# DM_V1_headers_misc.net
KiCad netlist of a schematic drawn in Altium Designer
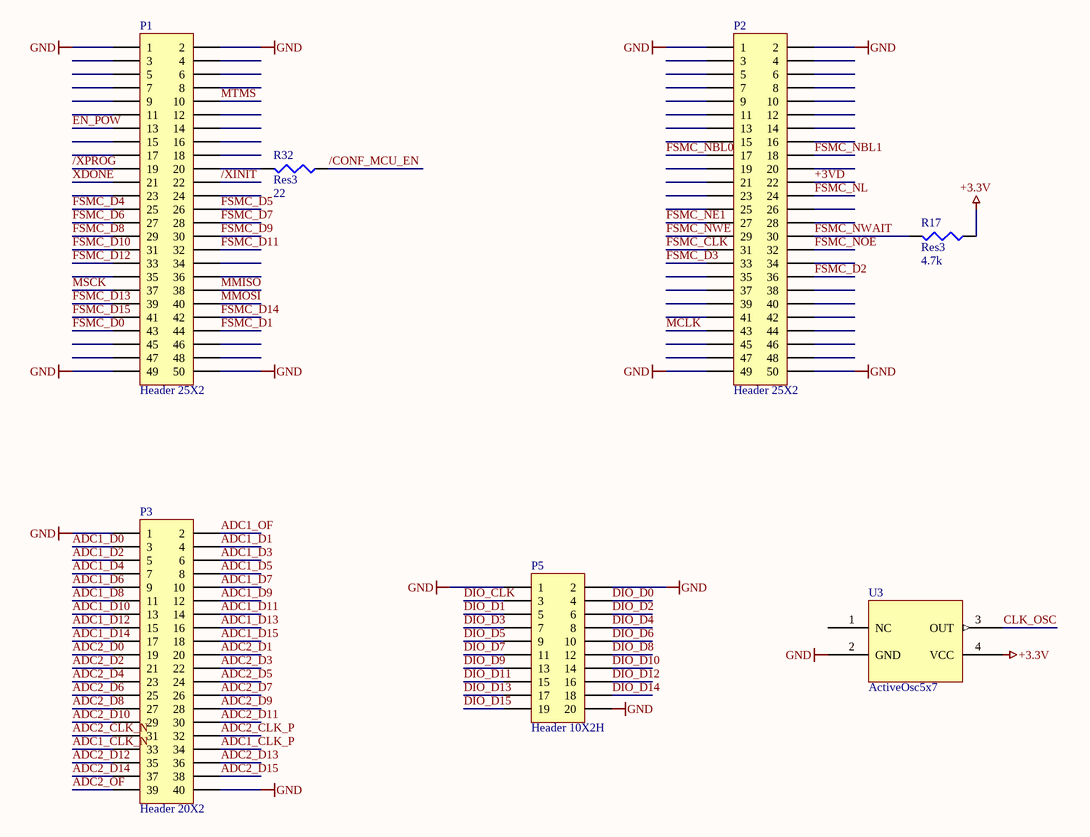
[diagram p0: DM_V1_headers_misc.SchDoc]

(export (version "E")
  (design (tool "Eeschema 10.0.6"))
  (components
    (comp (ref "P1")
      (value "Header 25X2")
      (footprint "HDR2X25")
      (description "Header, 25-Pin, Dual row")
      (fields (field (name "PUBLISHER") "Altium Limited"))
      (libsource (lib "Miscellaneous Connectors") (part "Header 25X2"))
    )
    (comp (ref "P2")
      (value "Header 25X2")
      (footprint "HDR2X25")
      (description "Header, 25-Pin, Dual row")
      (fields (field (name "PUBLISHER") "Altium Limited"))
      (libsource (lib "Miscellaneous Connectors") (part "Header 25X2"))
    )
    (comp (ref "P3")
      (value "Header 20X2")
      (footprint "HDR2X20")
      (description "Header, 20-Pin, Dual row")
      (fields (field (name "PUBLISHER") "Altium Limited"))
      (libsource (lib "Miscellaneous Connectors") (part "Header 20X2"))
    )
    (comp (ref "P5")
      (value "Header 10X2H")
      (footprint "HDR2X10H")
      (description "Header, 10-Pin, Dual row, Right Angle")
      (fields (field (name "PUBLISHER") "Altium Limited"))
      (libsource (lib "Miscellaneous Connectors") (part "Header 10X2H"))
    )
    (comp (ref "R17")
      (value "Res3")
      (footprint "J1-0603")
      (description "Resistor")
      (fields (field (name "ALTIUM_VALUE") "4.7k") (field (name "PUBLISHER") "Altium Limited"))
      (libsource (lib "Miscellaneous Devices") (part "Res3"))
    )
    (comp (ref "R32")
      (value "Res3")
      (footprint "J1-0603")
      (description "Resistor")
      (fields (field (name "ALTIUM_VALUE") "22") (field (name "PUBLISHER") "Altium Limited"))
      (libsource (lib "Miscellaneous Devices") (part "Res3"))
    )
    (comp (ref "U3")
      (value "ActiveOsc5x7")
      (footprint "ACT_OSC")
      (libsource (lib "Schlib2") (part "ActiveOsc5x7"))
    )
  )
  (nets
    (net (code "1") (name "+3.3V") (class "Default")
      (node (ref "R17") (pin "1") (pinfunction "1_1") (pintype "passive"))
      (node (ref "U3") (pin "4") (pinfunction "VCC_4") (pintype "power_in"))
    )
    (net (code "2") (name "/+3VD") (class "Default")
      (node (ref "P2") (pin "22") (pinfunction "22_22") (pintype "passive"))
    )
    (net (code "3") (name "/ADC1_CLK_N") (class "Default")
      (node (ref "P3") (pin "33") (pinfunction "33_33") (pintype "passive"))
    )
    (net (code "4") (name "/ADC1_CLK_P") (class "Default")
      (node (ref "P3") (pin "34") (pinfunction "34_34") (pintype "passive"))
    )
    (net (code "5") (name "/ADC1_D0") (class "Default")
      (node (ref "P3") (pin "3") (pinfunction "3_3") (pintype "passive"))
    )
    (net (code "6") (name "/ADC1_D1") (class "Default")
      (node (ref "P3") (pin "4") (pinfunction "4_4") (pintype "passive"))
    )
    (net (code "7") (name "/ADC1_D2") (class "Default")
      (node (ref "P3") (pin "5") (pinfunction "5_5") (pintype "passive"))
    )
    (net (code "8") (name "/ADC1_D3") (class "Default")
      (node (ref "P3") (pin "6") (pinfunction "6_6") (pintype "passive"))
    )
    (net (code "9") (name "/ADC1_D4") (class "Default")
      (node (ref "P3") (pin "7") (pinfunction "7_7") (pintype "passive"))
    )
    (net (code "10") (name "/ADC1_D5") (class "Default")
      (node (ref "P3") (pin "8") (pinfunction "8_8") (pintype "passive"))
    )
    (net (code "11") (name "/ADC1_D6") (class "Default")
      (node (ref "P3") (pin "9") (pinfunction "9_9") (pintype "passive"))
    )
    (net (code "12") (name "/ADC1_D7") (class "Default")
      (node (ref "P3") (pin "10") (pinfunction "10_10") (pintype "passive"))
    )
    (net (code "13") (name "/ADC1_D8") (class "Default")
      (node (ref "P3") (pin "11") (pinfunction "11_11") (pintype "passive"))
    )
    (net (code "14") (name "/ADC1_D9") (class "Default")
      (node (ref "P3") (pin "12") (pinfunction "12_12") (pintype "passive"))
    )
    (net (code "15") (name "/ADC1_D10") (class "Default")
      (node (ref "P3") (pin "13") (pinfunction "13_13") (pintype "passive"))
    )
    (net (code "16") (name "/ADC1_D11") (class "Default")
      (node (ref "P3") (pin "14") (pinfunction "14_14") (pintype "passive"))
    )
    (net (code "17") (name "/ADC1_D12") (class "Default")
      (node (ref "P3") (pin "15") (pinfunction "15_15") (pintype "passive"))
    )
    (net (code "18") (name "/ADC1_D13") (class "Default")
      (node (ref "P3") (pin "16") (pinfunction "16_16") (pintype "passive"))
    )
    (net (code "19") (name "/ADC1_D14") (class "Default")
      (node (ref "P3") (pin "17") (pinfunction "17_17") (pintype "passive"))
    )
    (net (code "20") (name "/ADC1_D15") (class "Default")
      (node (ref "P3") (pin "18") (pinfunction "18_18") (pintype "passive"))
    )
    (net (code "21") (name "/ADC1_OF") (class "Default")
      (node (ref "P3") (pin "2") (pinfunction "2_2") (pintype "passive"))
    )
    (net (code "22") (name "/ADC2_CLK_N") (class "Default")
      (node (ref "P3") (pin "31") (pinfunction "31_31") (pintype "passive"))
    )
    (net (code "23") (name "/ADC2_CLK_P") (class "Default")
      (node (ref "P3") (pin "32") (pinfunction "32_32") (pintype "passive"))
    )
    (net (code "24") (name "/ADC2_D0") (class "Default")
      (node (ref "P3") (pin "19") (pinfunction "19_19") (pintype "passive"))
    )
    (net (code "25") (name "/ADC2_D1") (class "Default")
      (node (ref "P3") (pin "20") (pinfunction "20_20") (pintype "passive"))
    )
    (net (code "26") (name "/ADC2_D2") (class "Default")
      (node (ref "P3") (pin "21") (pinfunction "21_21") (pintype "passive"))
    )
    (net (code "27") (name "/ADC2_D3") (class "Default")
      (node (ref "P3") (pin "22") (pinfunction "22_22") (pintype "passive"))
    )
    (net (code "28") (name "/ADC2_D4") (class "Default")
      (node (ref "P3") (pin "23") (pinfunction "23_23") (pintype "passive"))
    )
    (net (code "29") (name "/ADC2_D5") (class "Default")
      (node (ref "P3") (pin "24") (pinfunction "24_24") (pintype "passive"))
    )
    (net (code "30") (name "/ADC2_D6") (class "Default")
      (node (ref "P3") (pin "25") (pinfunction "25_25") (pintype "passive"))
    )
    (net (code "31") (name "/ADC2_D7") (class "Default")
      (node (ref "P3") (pin "26") (pinfunction "26_26") (pintype "passive"))
    )
    (net (code "32") (name "/ADC2_D8") (class "Default")
      (node (ref "P3") (pin "27") (pinfunction "27_27") (pintype "passive"))
    )
    (net (code "33") (name "/ADC2_D9") (class "Default")
      (node (ref "P3") (pin "28") (pinfunction "28_28") (pintype "passive"))
    )
    (net (code "34") (name "/ADC2_D10") (class "Default")
      (node (ref "P3") (pin "29") (pinfunction "29_29") (pintype "passive"))
    )
    (net (code "35") (name "/ADC2_D11") (class "Default")
      (node (ref "P3") (pin "30") (pinfunction "30_30") (pintype "passive"))
    )
    (net (code "36") (name "/ADC2_D12") (class "Default")
      (node (ref "P3") (pin "35") (pinfunction "35_35") (pintype "passive"))
    )
    (net (code "37") (name "/ADC2_D13") (class "Default")
      (node (ref "P3") (pin "36") (pinfunction "36_36") (pintype "passive"))
    )
    (net (code "38") (name "/ADC2_D14") (class "Default")
      (node (ref "P3") (pin "37") (pinfunction "37_37") (pintype "passive"))
    )
    (net (code "39") (name "/ADC2_D15") (class "Default")
      (node (ref "P3") (pin "38") (pinfunction "38_38") (pintype "passive"))
    )
    (net (code "40") (name "/ADC2_OF") (class "Default")
      (node (ref "P3") (pin "39") (pinfunction "39_39") (pintype "passive"))
    )
    (net (code "41") (name "/CLK_OSC") (class "Default")
      (node (ref "U3") (pin "3") (pinfunction "OUT_3") (pintype "output"))
    )
    (net (code "42") (name "/DIO_CLK") (class "Default")
      (node (ref "P5") (pin "3") (pinfunction "3_3") (pintype "passive"))
    )
    (net (code "43") (name "/DIO_D0") (class "Default")
      (node (ref "P5") (pin "4") (pinfunction "4_4") (pintype "passive"))
    )
    (net (code "44") (name "/DIO_D1") (class "Default")
      (node (ref "P5") (pin "5") (pinfunction "5_5") (pintype "passive"))
    )
    (net (code "45") (name "/DIO_D2") (class "Default")
      (node (ref "P5") (pin "6") (pinfunction "6_6") (pintype "passive"))
    )
    (net (code "46") (name "/DIO_D3") (class "Default")
      (node (ref "P5") (pin "7") (pinfunction "7_7") (pintype "passive"))
    )
    (net (code "47") (name "/DIO_D4") (class "Default")
      (node (ref "P5") (pin "8") (pinfunction "8_8") (pintype "passive"))
    )
    (net (code "48") (name "/DIO_D5") (class "Default")
      (node (ref "P5") (pin "9") (pinfunction "9_9") (pintype "passive"))
    )
    (net (code "49") (name "/DIO_D6") (class "Default")
      (node (ref "P5") (pin "10") (pinfunction "10_10") (pintype "passive"))
    )
    (net (code "50") (name "/DIO_D7") (class "Default")
      (node (ref "P5") (pin "11") (pinfunction "11_11") (pintype "passive"))
    )
    (net (code "51") (name "/DIO_D8") (class "Default")
      (node (ref "P5") (pin "12") (pinfunction "12_12") (pintype "passive"))
    )
    (net (code "52") (name "/DIO_D9") (class "Default")
      (node (ref "P5") (pin "13") (pinfunction "13_13") (pintype "passive"))
    )
    (net (code "53") (name "/DIO_D10") (class "Default")
      (node (ref "P5") (pin "14") (pinfunction "14_14") (pintype "passive"))
    )
    (net (code "54") (name "/DIO_D11") (class "Default")
      (node (ref "P5") (pin "15") (pinfunction "15_15") (pintype "passive"))
    )
    (net (code "55") (name "/DIO_D12") (class "Default")
      (node (ref "P5") (pin "16") (pinfunction "16_16") (pintype "passive"))
    )
    (net (code "56") (name "/DIO_D13") (class "Default")
      (node (ref "P5") (pin "17") (pinfunction "17_17") (pintype "passive"))
    )
    (net (code "57") (name "/DIO_D14") (class "Default")
      (node (ref "P5") (pin "18") (pinfunction "18_18") (pintype "passive"))
    )
    (net (code "58") (name "/DIO_D15") (class "Default")
      (node (ref "P5") (pin "19") (pinfunction "19_19") (pintype "passive"))
    )
    (net (code "59") (name "/EN_POW") (class "Default")
      (node (ref "P1") (pin "13") (pinfunction "13_13") (pintype "passive"))
    )
    (net (code "60") (name "/FSMC_CLK") (class "Default")
      (node (ref "P2") (pin "31") (pinfunction "31_31") (pintype "passive"))
    )
    (net (code "61") (name "/FSMC_D0") (class "Default")
      (node (ref "P1") (pin "43") (pinfunction "43_43") (pintype "passive"))
    )
    (net (code "62") (name "/FSMC_D1") (class "Default")
      (node (ref "P1") (pin "44") (pinfunction "44_44") (pintype "passive"))
    )
    (net (code "63") (name "/FSMC_D2") (class "Default")
      (node (ref "P2") (pin "36") (pinfunction "36_36") (pintype "passive"))
    )
    (net (code "64") (name "/FSMC_D3") (class "Default")
      (node (ref "P2") (pin "33") (pinfunction "33_33") (pintype "passive"))
    )
    (net (code "65") (name "/FSMC_D4") (class "Default")
      (node (ref "P1") (pin "25") (pinfunction "25_25") (pintype "passive"))
    )
    (net (code "66") (name "/FSMC_D5") (class "Default")
      (node (ref "P1") (pin "26") (pinfunction "26_26") (pintype "passive"))
    )
    (net (code "67") (name "/FSMC_D6") (class "Default")
      (node (ref "P1") (pin "27") (pinfunction "27_27") (pintype "passive"))
    )
    (net (code "68") (name "/FSMC_D7") (class "Default")
      (node (ref "P1") (pin "28") (pinfunction "28_28") (pintype "passive"))
    )
    (net (code "69") (name "/FSMC_D8") (class "Default")
      (node (ref "P1") (pin "29") (pinfunction "29_29") (pintype "passive"))
    )
    (net (code "70") (name "/FSMC_D9") (class "Default")
      (node (ref "P1") (pin "30") (pinfunction "30_30") (pintype "passive"))
    )
    (net (code "71") (name "/FSMC_D10") (class "Default")
      (node (ref "P1") (pin "31") (pinfunction "31_31") (pintype "passive"))
    )
    (net (code "72") (name "/FSMC_D11") (class "Default")
      (node (ref "P1") (pin "32") (pinfunction "32_32") (pintype "passive"))
    )
    (net (code "73") (name "/FSMC_D12") (class "Default")
      (node (ref "P1") (pin "33") (pinfunction "33_33") (pintype "passive"))
    )
    (net (code "74") (name "/FSMC_D13") (class "Default")
      (node (ref "P1") (pin "39") (pinfunction "39_39") (pintype "passive"))
    )
    (net (code "75") (name "/FSMC_D14") (class "Default")
      (node (ref "P1") (pin "42") (pinfunction "42_42") (pintype "passive"))
    )
    (net (code "76") (name "/FSMC_D15") (class "Default")
      (node (ref "P1") (pin "41") (pinfunction "41_41") (pintype "passive"))
    )
    (net (code "77") (name "/FSMC_NBL0") (class "Default")
      (node (ref "P2") (pin "17") (pinfunction "17_17") (pintype "passive"))
    )
    (net (code "78") (name "/FSMC_NBL1") (class "Default")
      (node (ref "P2") (pin "18") (pinfunction "18_18") (pintype "passive"))
    )
    (net (code "79") (name "/FSMC_NE1") (class "Default")
      (node (ref "P2") (pin "27") (pinfunction "27_27") (pintype "passive"))
    )
    (net (code "80") (name "/FSMC_NL") (class "Default")
      (node (ref "P2") (pin "24") (pinfunction "24_24") (pintype "passive"))
    )
    (net (code "81") (name "/FSMC_NOE") (class "Default")
      (node (ref "P2") (pin "32") (pinfunction "32_32") (pintype "passive"))
    )
    (net (code "82") (name "/FSMC_NWAIT") (class "Default")
      (node (ref "P2") (pin "30") (pinfunction "30_30") (pintype "passive"))
      (node (ref "R17") (pin "2") (pinfunction "2_2") (pintype "passive"))
    )
    (net (code "83") (name "/FSMC_NWE") (class "Default")
      (node (ref "P2") (pin "29") (pinfunction "29_29") (pintype "passive"))
    )
    (net (code "84") (name "/MCLK") (class "Default")
      (node (ref "P2") (pin "43") (pinfunction "43_43") (pintype "passive"))
    )
    (net (code "85") (name "/MMISO") (class "Default")
      (node (ref "P1") (pin "38") (pinfunction "38_38") (pintype "passive"))
    )
    (net (code "86") (name "/MMOSI") (class "Default")
      (node (ref "P1") (pin "40") (pinfunction "40_40") (pintype "passive"))
    )
    (net (code "87") (name "/MSCK") (class "Default")
      (node (ref "P1") (pin "37") (pinfunction "37_37") (pintype "passive"))
    )
    (net (code "88") (name "/MTMS") (class "Default")
      (node (ref "P1") (pin "10") (pinfunction "10_10") (pintype "passive"))
    )
    (net (code "89") (name "/XDONE") (class "Default")
      (node (ref "P1") (pin "21") (pinfunction "21_21") (pintype "passive"))
    )
    (net (code "90") (name "/{slash}CONF_MCU_EN") (class "Default")
      (node (ref "R32") (pin "1") (pinfunction "1_1") (pintype "passive"))
    )
    (net (code "91") (name "/{slash}XINIT") (class "Default")
      (node (ref "P1") (pin "22") (pinfunction "22_22") (pintype "passive"))
    )
    (net (code "92") (name "/{slash}XPROG") (class "Default")
      (node (ref "P1") (pin "19") (pinfunction "19_19") (pintype "passive"))
    )
    (net (code "93") (name "GND") (class "Default")
      (node (ref "P1") (pin "1") (pinfunction "1_1") (pintype "passive"))
      (node (ref "P1") (pin "2") (pinfunction "2_2") (pintype "passive"))
      (node (ref "P1") (pin "49") (pinfunction "49_49") (pintype "passive"))
      (node (ref "P1") (pin "50") (pinfunction "50_50") (pintype "passive"))
      (node (ref "P2") (pin "1") (pinfunction "1_1") (pintype "passive"))
      (node (ref "P2") (pin "2") (pinfunction "2_2") (pintype "passive"))
      (node (ref "P2") (pin "49") (pinfunction "49_49") (pintype "passive"))
      (node (ref "P2") (pin "50") (pinfunction "50_50") (pintype "passive"))
      (node (ref "P3") (pin "1") (pinfunction "1_1") (pintype "passive"))
      (node (ref "P3") (pin "40") (pinfunction "40_40") (pintype "passive"))
      (node (ref "P5") (pin "1") (pinfunction "1_1") (pintype "passive"))
      (node (ref "P5") (pin "2") (pinfunction "2_2") (pintype "passive"))
      (node (ref "P5") (pin "20") (pinfunction "20_20") (pintype "passive"))
      (node (ref "U3") (pin "2") (pinfunction "GND_2") (pintype "power_in"))
    )
    (net (code "94") (name "Net-(P1-Pad20)") (class "Default")
      (node (ref "P1") (pin "20") (pinfunction "20_20") (pintype "passive"))
      (node (ref "R32") (pin "2") (pinfunction "2_2") (pintype "passive"))
    )
    (net (code "95") (name "unconnected-(P1-Pad3)") (class "Default")
      (node (ref "P1") (pin "3") (pinfunction "3_3") (pintype "passive"))
    )
    (net (code "96") (name "unconnected-(P1-Pad4)") (class "Default")
      (node (ref "P1") (pin "4") (pinfunction "4_4") (pintype "passive"))
    )
    (net (code "97") (name "unconnected-(P1-Pad5)") (class "Default")
      (node (ref "P1") (pin "5") (pinfunction "5_5") (pintype "passive"))
    )
    (net (code "98") (name "unconnected-(P1-Pad6)") (class "Default")
      (node (ref "P1") (pin "6") (pinfunction "6_6") (pintype "passive"))
    )
    (net (code "99") (name "unconnected-(P1-Pad7)") (class "Default")
      (node (ref "P1") (pin "7") (pinfunction "7_7") (pintype "passive"))
    )
    (net (code "100") (name "unconnected-(P1-Pad8)") (class "Default")
      (node (ref "P1") (pin "8") (pinfunction "8_8") (pintype "passive"))
    )
    (net (code "101") (name "unconnected-(P1-Pad9)") (class "Default")
      (node (ref "P1") (pin "9") (pinfunction "9_9") (pintype "passive"))
    )
    (net (code "102") (name "unconnected-(P1-Pad11)") (class "Default")
      (node (ref "P1") (pin "11") (pinfunction "11_11") (pintype "passive"))
    )
    (net (code "103") (name "unconnected-(P1-Pad12)") (class "Default")
      (node (ref "P1") (pin "12") (pinfunction "12_12") (pintype "passive"))
    )
    (net (code "104") (name "unconnected-(P1-Pad14)") (class "Default")
      (node (ref "P1") (pin "14") (pinfunction "14_14") (pintype "passive"))
    )
    (net (code "105") (name "unconnected-(P1-Pad15)") (class "Default")
      (node (ref "P1") (pin "15") (pinfunction "15_15") (pintype "passive"))
    )
    (net (code "106") (name "unconnected-(P1-Pad16)") (class "Default")
      (node (ref "P1") (pin "16") (pinfunction "16_16") (pintype "passive"))
    )
    (net (code "107") (name "unconnected-(P1-Pad17)") (class "Default")
      (node (ref "P1") (pin "17") (pinfunction "17_17") (pintype "passive"))
    )
    (net (code "108") (name "unconnected-(P1-Pad18)") (class "Default")
      (node (ref "P1") (pin "18") (pinfunction "18_18") (pintype "passive"))
    )
    (net (code "109") (name "unconnected-(P1-Pad23)") (class "Default")
      (node (ref "P1") (pin "23") (pinfunction "23_23") (pintype "passive"))
    )
    (net (code "110") (name "unconnected-(P1-Pad24)") (class "Default")
      (node (ref "P1") (pin "24") (pinfunction "24_24") (pintype "passive"))
    )
    (net (code "111") (name "unconnected-(P1-Pad34)") (class "Default")
      (node (ref "P1") (pin "34") (pinfunction "34_34") (pintype "passive"))
    )
    (net (code "112") (name "unconnected-(P1-Pad35)") (class "Default")
      (node (ref "P1") (pin "35") (pinfunction "35_35") (pintype "passive"))
    )
    (net (code "113") (name "unconnected-(P1-Pad36)") (class "Default")
      (node (ref "P1") (pin "36") (pinfunction "36_36") (pintype "passive"))
    )
    (net (code "114") (name "unconnected-(P1-Pad45)") (class "Default")
      (node (ref "P1") (pin "45") (pinfunction "45_45") (pintype "passive"))
    )
    (net (code "115") (name "unconnected-(P1-Pad46)") (class "Default")
      (node (ref "P1") (pin "46") (pinfunction "46_46") (pintype "passive"))
    )
    (net (code "116") (name "unconnected-(P1-Pad47)") (class "Default")
      (node (ref "P1") (pin "47") (pinfunction "47_47") (pintype "passive"))
    )
    (net (code "117") (name "unconnected-(P1-Pad48)") (class "Default")
      (node (ref "P1") (pin "48") (pinfunction "48_48") (pintype "passive"))
    )
    (net (code "118") (name "unconnected-(P2-Pad3)") (class "Default")
      (node (ref "P2") (pin "3") (pinfunction "3_3") (pintype "passive"))
    )
    (net (code "119") (name "unconnected-(P2-Pad4)") (class "Default")
      (node (ref "P2") (pin "4") (pinfunction "4_4") (pintype "passive"))
    )
    (net (code "120") (name "unconnected-(P2-Pad5)") (class "Default")
      (node (ref "P2") (pin "5") (pinfunction "5_5") (pintype "passive"))
    )
    (net (code "121") (name "unconnected-(P2-Pad6)") (class "Default")
      (node (ref "P2") (pin "6") (pinfunction "6_6") (pintype "passive"))
    )
    (net (code "122") (name "unconnected-(P2-Pad7)") (class "Default")
      (node (ref "P2") (pin "7") (pinfunction "7_7") (pintype "passive"))
    )
    (net (code "123") (name "unconnected-(P2-Pad8)") (class "Default")
      (node (ref "P2") (pin "8") (pinfunction "8_8") (pintype "passive"))
    )
    (net (code "124") (name "unconnected-(P2-Pad9)") (class "Default")
      (node (ref "P2") (pin "9") (pinfunction "9_9") (pintype "passive"))
    )
    (net (code "125") (name "unconnected-(P2-Pad10)") (class "Default")
      (node (ref "P2") (pin "10") (pinfunction "10_10") (pintype "passive"))
    )
    (net (code "126") (name "unconnected-(P2-Pad11)") (class "Default")
      (node (ref "P2") (pin "11") (pinfunction "11_11") (pintype "passive"))
    )
    (net (code "127") (name "unconnected-(P2-Pad12)") (class "Default")
      (node (ref "P2") (pin "12") (pinfunction "12_12") (pintype "passive"))
    )
    (net (code "128") (name "unconnected-(P2-Pad13)") (class "Default")
      (node (ref "P2") (pin "13") (pinfunction "13_13") (pintype "passive"))
    )
    (net (code "129") (name "unconnected-(P2-Pad14)") (class "Default")
      (node (ref "P2") (pin "14") (pinfunction "14_14") (pintype "passive"))
    )
    (net (code "130") (name "unconnected-(P2-Pad15)") (class "Default")
      (node (ref "P2") (pin "15") (pinfunction "15_15") (pintype "passive"))
    )
    (net (code "131") (name "unconnected-(P2-Pad16)") (class "Default")
      (node (ref "P2") (pin "16") (pinfunction "16_16") (pintype "passive"))
    )
    (net (code "132") (name "unconnected-(P2-Pad19)") (class "Default")
      (node (ref "P2") (pin "19") (pinfunction "19_19") (pintype "passive"))
    )
    (net (code "133") (name "unconnected-(P2-Pad20)") (class "Default")
      (node (ref "P2") (pin "20") (pinfunction "20_20") (pintype "passive"))
    )
    (net (code "134") (name "unconnected-(P2-Pad21)") (class "Default")
      (node (ref "P2") (pin "21") (pinfunction "21_21") (pintype "passive"))
    )
    (net (code "135") (name "unconnected-(P2-Pad23)") (class "Default")
      (node (ref "P2") (pin "23") (pinfunction "23_23") (pintype "passive"))
    )
    (net (code "136") (name "unconnected-(P2-Pad25)") (class "Default")
      (node (ref "P2") (pin "25") (pinfunction "25_25") (pintype "passive"))
    )
    (net (code "137") (name "unconnected-(P2-Pad26)") (class "Default")
      (node (ref "P2") (pin "26") (pinfunction "26_26") (pintype "passive"))
    )
    (net (code "138") (name "unconnected-(P2-Pad28)") (class "Default")
      (node (ref "P2") (pin "28") (pinfunction "28_28") (pintype "passive"))
    )
    (net (code "139") (name "unconnected-(P2-Pad34)") (class "Default")
      (node (ref "P2") (pin "34") (pinfunction "34_34") (pintype "passive"))
    )
    (net (code "140") (name "unconnected-(P2-Pad35)") (class "Default")
      (node (ref "P2") (pin "35") (pinfunction "35_35") (pintype "passive"))
    )
    (net (code "141") (name "unconnected-(P2-Pad37)") (class "Default")
      (node (ref "P2") (pin "37") (pinfunction "37_37") (pintype "passive"))
    )
    (net (code "142") (name "unconnected-(P2-Pad38)") (class "Default")
      (node (ref "P2") (pin "38") (pinfunction "38_38") (pintype "passive"))
    )
    (net (code "143") (name "unconnected-(P2-Pad39)") (class "Default")
      (node (ref "P2") (pin "39") (pinfunction "39_39") (pintype "passive"))
    )
    (net (code "144") (name "unconnected-(P2-Pad40)") (class "Default")
      (node (ref "P2") (pin "40") (pinfunction "40_40") (pintype "passive"))
    )
    (net (code "145") (name "unconnected-(P2-Pad41)") (class "Default")
      (node (ref "P2") (pin "41") (pinfunction "41_41") (pintype "passive"))
    )
    (net (code "146") (name "unconnected-(P2-Pad42)") (class "Default")
      (node (ref "P2") (pin "42") (pinfunction "42_42") (pintype "passive"))
    )
    (net (code "147") (name "unconnected-(P2-Pad44)") (class "Default")
      (node (ref "P2") (pin "44") (pinfunction "44_44") (pintype "passive"))
    )
    (net (code "148") (name "unconnected-(P2-Pad45)") (class "Default")
      (node (ref "P2") (pin "45") (pinfunction "45_45") (pintype "passive"))
    )
    (net (code "149") (name "unconnected-(P2-Pad46)") (class "Default")
      (node (ref "P2") (pin "46") (pinfunction "46_46") (pintype "passive"))
    )
    (net (code "150") (name "unconnected-(P2-Pad47)") (class "Default")
      (node (ref "P2") (pin "47") (pinfunction "47_47") (pintype "passive"))
    )
    (net (code "151") (name "unconnected-(P2-Pad48)") (class "Default")
      (node (ref "P2") (pin "48") (pinfunction "48_48") (pintype "passive"))
    )
    (net (code "152") (name "unconnected-(U3-NC-Pad1)") (class "Default")
      (node (ref "U3") (pin "1") (pinfunction "NC_1") (pintype "tri_state"))
    )
  )
)
